# SOIC8_to_DIP.net
KiCad netlist of a schematic drawn in EAGLE
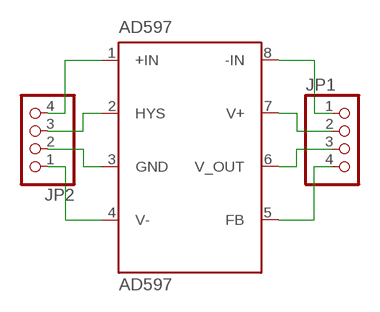
[diagram p0: schematic, sheet 1]

(export (version "E")
  (design (tool "Eeschema 10.0.6"))
  (components
    (comp (ref "AD597")
      (value "AD597")
      (footprint "eagle-import:SO8")
      (libsource (lib "eagle-import") (part "AD597"))
    )
    (comp (ref "JP1")
      (value "PINHD-1X4")
      (footprint "eagle-import:1X04")
      (libsource (lib "eagle-import") (part "PINHD-1X4"))
    )
    (comp (ref "JP2")
      (value "PINHD-1X4")
      (footprint "eagle-import:1X04")
      (libsource (lib "eagle-import") (part "PINHD-1X4"))
    )
  )
  (nets
    (net (code "1") (name "Net-(AD597-+IN)") (class "Default")
      (node (ref "AD597") (pin "1") (pinfunction "+IN_1") (pintype "input"))
      (node (ref "JP2") (pin "4") (pinfunction "4_4") (pintype "passive"))
    )
    (net (code "2") (name "Net-(AD597--IN)") (class "Default")
      (node (ref "AD597") (pin "8") (pinfunction "-IN_8") (pintype "power_in"))
      (node (ref "JP1") (pin "1") (pinfunction "1_1") (pintype "passive"))
    )
    (net (code "3") (name "Net-(AD597-FB)") (class "Default")
      (node (ref "AD597") (pin "5") (pinfunction "FB_5") (pintype "power_in"))
      (node (ref "JP1") (pin "4") (pinfunction "4_4") (pintype "passive"))
    )
    (net (code "4") (name "Net-(AD597-GND)") (class "Default")
      (node (ref "AD597") (pin "3") (pinfunction "GND_3") (pintype "passive"))
      (node (ref "JP2") (pin "2") (pinfunction "2_2") (pintype "passive"))
    )
    (net (code "5") (name "Net-(AD597-HYS)") (class "Default")
      (node (ref "AD597") (pin "2") (pinfunction "HYS_2") (pintype "input"))
      (node (ref "JP2") (pin "3") (pinfunction "3_3") (pintype "passive"))
    )
    (net (code "6") (name "Net-(AD597-V+)") (class "Default")
      (node (ref "AD597") (pin "7") (pinfunction "V+_7") (pintype "passive"))
      (node (ref "JP1") (pin "2") (pinfunction "2_2") (pintype "passive"))
    )
    (net (code "7") (name "Net-(AD597-V-)") (class "Default")
      (node (ref "AD597") (pin "4") (pinfunction "V-_4") (pintype "passive"))
      (node (ref "JP2") (pin "1") (pinfunction "1_1") (pintype "passive"))
    )
    (net (code "8") (name "Net-(AD597-V_OUT)") (class "Default")
      (node (ref "AD597") (pin "6") (pinfunction "V_OUT_6") (pintype "passive"))
      (node (ref "JP1") (pin "3") (pinfunction "3_3") (pintype "passive"))
    )
  )
)
